# Sheet1.net
KiCad netlist of a schematic drawn in Altium Designer
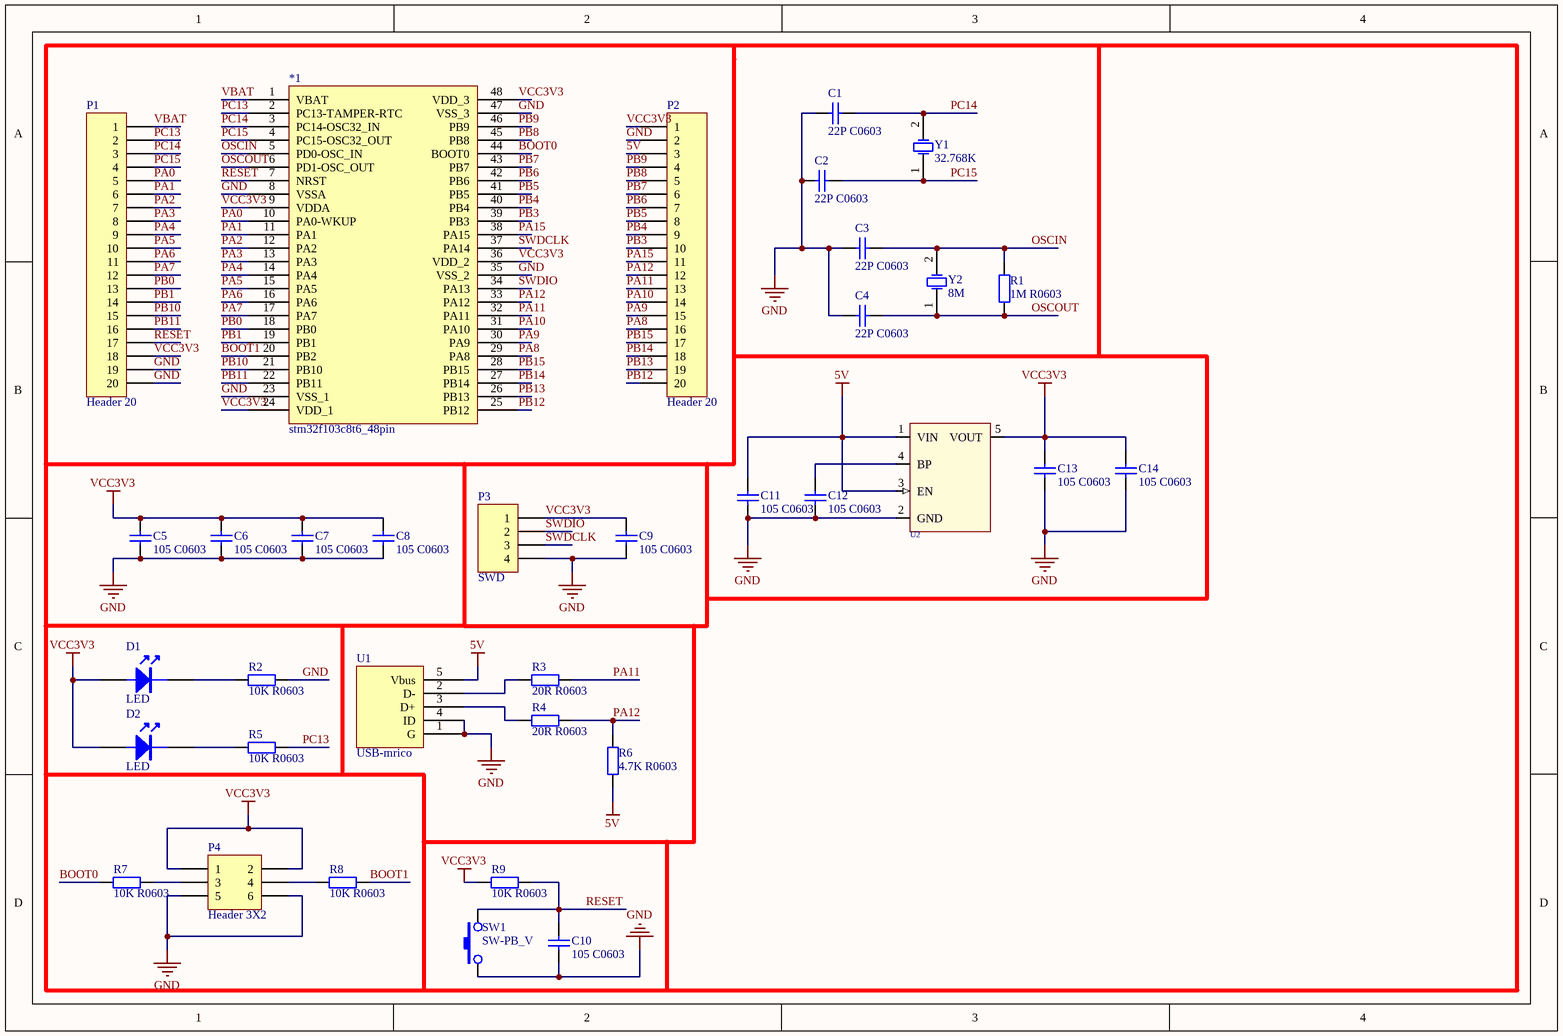
[diagram p0: Sheet1.SchDoc]

(export (version "E")
  (design (tool "Eeschema 10.0.6"))
  (components
    (comp (ref "*1")
      (value "stm32f103c8t6_48pin")
      (footprint "TQFP48 7x7_L")
      (libsource (lib "stm32原理图库") (part "stm32f103c8t6_48pin"))
    )
    (comp (ref "C1")
      (value "22P C0603")
      (footprint "C 0603")
      (fields (field (name "PUBLISHER") "Altium Limited"))
      (libsource (lib "stm32原理图库") (part "Cap"))
    )
    (comp (ref "C2")
      (value "22P C0603")
      (footprint "C 0603")
      (fields (field (name "PUBLISHER") "Altium Limited"))
      (libsource (lib "stm32原理图库") (part "Cap"))
    )
    (comp (ref "C3")
      (value "22P C0603")
      (footprint "C 0603")
      (fields (field (name "PUBLISHER") "Altium Limited"))
      (libsource (lib "stm32原理图库") (part "Cap"))
    )
    (comp (ref "C4")
      (value "22P C0603")
      (footprint "C 0603")
      (fields (field (name "PUBLISHER") "Altium Limited"))
      (libsource (lib "stm32原理图库") (part "Cap"))
    )
    (comp (ref "C5")
      (value "105 C0603")
      (footprint "C 0603")
      (fields (field (name "PUBLISHER") "Altium Limited"))
      (libsource (lib "stm32原理图库") (part "Cap"))
    )
    (comp (ref "C6")
      (value "105 C0603")
      (footprint "C 0603")
      (fields (field (name "PUBLISHER") "Altium Limited"))
      (libsource (lib "stm32原理图库") (part "Cap"))
    )
    (comp (ref "C7")
      (value "105 C0603")
      (footprint "C 0603")
      (fields (field (name "PUBLISHER") "Altium Limited"))
      (libsource (lib "stm32原理图库") (part "Cap"))
    )
    (comp (ref "C8")
      (value "105 C0603")
      (footprint "C 0603")
      (fields (field (name "PUBLISHER") "Altium Limited"))
      (libsource (lib "stm32原理图库") (part "Cap"))
    )
    (comp (ref "C9")
      (value "105 C0603")
      (footprint "C 0603")
      (fields (field (name "PUBLISHER") "Altium Limited"))
      (libsource (lib "stm32原理图库") (part "Cap"))
    )
    (comp (ref "C10")
      (value "105 C0603")
      (footprint "C 0603")
      (fields (field (name "PUBLISHER") "Altium Limited"))
      (libsource (lib "stm32原理图库") (part "Cap"))
    )
    (comp (ref "C11")
      (value "105 C0603")
      (footprint "C 0603")
      (fields (field (name "PUBLISHER") "Altium Limited"))
      (libsource (lib "stm32原理图库") (part "Cap"))
    )
    (comp (ref "C12")
      (value "105 C0603")
      (footprint "C 0603")
      (fields (field (name "PUBLISHER") "Altium Limited"))
      (libsource (lib "stm32原理图库") (part "Cap"))
    )
    (comp (ref "C13")
      (value "105 C0603")
      (footprint "C 0603")
      (fields (field (name "PUBLISHER") "Altium Limited"))
      (libsource (lib "stm32原理图库") (part "Cap"))
    )
    (comp (ref "C14")
      (value "105 C0603")
      (footprint "C 0603")
      (fields (field (name "PUBLISHER") "Altium Limited"))
      (libsource (lib "stm32原理图库") (part "Cap"))
    )
    (comp (ref "D1") (value "LED") (footprint "LED 0805G") (libsource (lib "stm32原理图库") (part "LED")))
    (comp (ref "D2") (value "LED") (footprint "LED 0805G") (libsource (lib "stm32原理图库") (part "LED")))
    (comp (ref "P1")
      (value "Header 20")
      (footprint "HDR1X20")
      (fields (field (name "PUBLISHER") "Altium Limited"))
      (libsource (lib "stm32原理图库") (part "Header1* 20"))
    )
    (comp (ref "P2")
      (value "Header 20")
      (footprint "HDR1X20")
      (fields (field (name "PUBLISHER") "Altium Limited"))
      (libsource (lib "") (part "Header1* 20_1"))
    )
    (comp (ref "P3")
      (value "SWD")
      (footprint "HDR-1X4_H")
      (fields (field (name "PUBLISHER") "Altium Limited"))
      (libsource (lib "stm32原理图库") (part "Header 1*4"))
    )
    (comp (ref "P4")
      (value "Header 3X2")
      (footprint "HDR-3X2")
      (fields (field (name "PUBLISHER") "Altium Limited"))
      (libsource (lib "stm32原理图库") (part "Header 2*3"))
    )
    (comp (ref "R1")
      (value "1M R0603")
      (footprint "R 0603")
      (fields (field (name "PUBLISHER") "Altium Limited"))
      (libsource (lib "") (part "Res2_1"))
    )
    (comp (ref "R2")
      (value "10K R0603")
      (footprint "R 0603")
      (fields (field (name "PUBLISHER") "Altium Limited"))
      (libsource (lib "stm32原理图库") (part "Res2"))
    )
    (comp (ref "R3")
      (value "20R R0603")
      (footprint "R 0603")
      (fields (field (name "PUBLISHER") "Altium Limited"))
      (libsource (lib "stm32原理图库") (part "Res2"))
    )
    (comp (ref "R4")
      (value "20R R0603")
      (footprint "R 0603")
      (fields (field (name "PUBLISHER") "Altium Limited"))
      (libsource (lib "stm32原理图库") (part "Res2"))
    )
    (comp (ref "R5")
      (value "10K R0603")
      (footprint "R 0603")
      (fields (field (name "PUBLISHER") "Altium Limited"))
      (libsource (lib "stm32原理图库") (part "Res2"))
    )
    (comp (ref "R6")
      (value "4.7K R0603")
      (footprint "R 0603")
      (fields (field (name "PUBLISHER") "Altium Limited"))
      (libsource (lib "") (part "Res2_1"))
    )
    (comp (ref "R7")
      (value "10K R0603")
      (footprint "R 0603")
      (fields (field (name "PUBLISHER") "Altium Limited"))
      (libsource (lib "stm32原理图库") (part "Res2"))
    )
    (comp (ref "R8")
      (value "10K R0603")
      (footprint "R 0603")
      (fields (field (name "PUBLISHER") "Altium Limited"))
      (libsource (lib "stm32原理图库") (part "Res2"))
    )
    (comp (ref "R9")
      (value "10K R0603")
      (footprint "R 0603")
      (fields (field (name "PUBLISHER") "Altium Limited"))
      (libsource (lib "stm32原理图库") (part "Res2"))
    )
    (comp (ref "SW1")
      (value "SW-PB_V")
      (footprint "TSW SMD-3*6*2.5")
      (libsource (lib "stm32原理图库") (part "SW-PB_V"))
    )
    (comp (ref "U1")
      (value "USB-mrico")
      (footprint "USB-micro_B")
      (libsource (lib "stm32原理图库") (part "usb-STM"))
    )
    (comp (ref "U2")
      (value "RT9193")
      (footprint "SOT23-5L")
      (fields (field (name "ICA_PARTNUM") "$$2191094$$RT9193-15CU5") (field (name "PART NUMBER") "TMP-13"))
      (libsource (lib "stm32原理图库") (part "RT9193X_5P"))
    )
    (comp (ref "Y1")
      (value "32.768K")
      (footprint "XTAL-49S DIP")
      (fields (field (name "PUBLISHER") "Altium Limited"))
      (libsource (lib "stm32原理图库") (part "XTAL"))
    )
    (comp (ref "Y2")
      (value "8M")
      (footprint "XTAL-49S DIP")
      (fields (field (name "PUBLISHER") "Altium Limited"))
      (libsource (lib "stm32原理图库") (part "XTAL"))
    )
  )
  (nets
    (net (code "1") (name "/BOOT0") (class "Default")
      (node (ref "*1") (pin "44") (pinfunction "BOOT0_44") (pintype "passive"))
      (node (ref "R7") (pin "1") (pinfunction "1_1") (pintype "passive"))
    )
    (net (code "2") (name "/BOOT1") (class "Default")
      (node (ref "*1") (pin "20") (pinfunction "PB2_20") (pintype "passive"))
      (node (ref "R8") (pin "2") (pinfunction "2_2") (pintype "passive"))
    )
    (net (code "3") (name "/OSCIN") (class "Default")
      (node (ref "*1") (pin "5") (pinfunction "PD0-OSC_IN_5") (pintype "passive"))
      (node (ref "C3") (pin "2") (pinfunction "2_2") (pintype "passive"))
      (node (ref "R1") (pin "2") (pinfunction "2_2") (pintype "passive"))
      (node (ref "Y2") (pin "2") (pinfunction "OSC2_2") (pintype "passive"))
    )
    (net (code "4") (name "/OSCOUT") (class "Default")
      (node (ref "*1") (pin "6") (pinfunction "PD1-OSC_OUT_6") (pintype "passive"))
      (node (ref "C4") (pin "2") (pinfunction "2_2") (pintype "passive"))
      (node (ref "R1") (pin "1") (pinfunction "1_1") (pintype "passive"))
      (node (ref "Y2") (pin "1") (pinfunction "OSC1_1") (pintype "passive"))
    )
    (net (code "5") (name "/PA0") (class "Default")
      (node (ref "*1") (pin "10") (pinfunction "PA0-WKUP_10") (pintype "passive"))
      (node (ref "P1") (pin "5") (pinfunction "5_5") (pintype "passive"))
    )
    (net (code "6") (name "/PA1") (class "Default")
      (node (ref "*1") (pin "11") (pinfunction "PA1_11") (pintype "passive"))
      (node (ref "P1") (pin "6") (pinfunction "6_6") (pintype "passive"))
    )
    (net (code "7") (name "/PA2") (class "Default")
      (node (ref "*1") (pin "12") (pinfunction "PA2_12") (pintype "passive"))
      (node (ref "P1") (pin "7") (pinfunction "7_7") (pintype "passive"))
    )
    (net (code "8") (name "/PA3") (class "Default")
      (node (ref "*1") (pin "13") (pinfunction "PA3_13") (pintype "passive"))
      (node (ref "P1") (pin "8") (pinfunction "8_8") (pintype "passive"))
    )
    (net (code "9") (name "/PA4") (class "Default")
      (node (ref "*1") (pin "14") (pinfunction "PA4_14") (pintype "passive"))
      (node (ref "P1") (pin "9") (pinfunction "9_9") (pintype "passive"))
    )
    (net (code "10") (name "/PA5") (class "Default")
      (node (ref "*1") (pin "15") (pinfunction "PA5_15") (pintype "passive"))
      (node (ref "P1") (pin "10") (pinfunction "10_10") (pintype "passive"))
    )
    (net (code "11") (name "/PA6") (class "Default")
      (node (ref "*1") (pin "16") (pinfunction "PA6_16") (pintype "passive"))
      (node (ref "P1") (pin "11") (pinfunction "11_11") (pintype "passive"))
    )
    (net (code "12") (name "/PA7") (class "Default")
      (node (ref "*1") (pin "17") (pinfunction "PA7_17") (pintype "passive"))
      (node (ref "P1") (pin "12") (pinfunction "12_12") (pintype "passive"))
    )
    (net (code "13") (name "/PA8") (class "Default")
      (node (ref "*1") (pin "29") (pinfunction "PA8_29") (pintype "passive"))
      (node (ref "P2") (pin "16") (pinfunction "16_16") (pintype "passive"))
    )
    (net (code "14") (name "/PA9") (class "Default")
      (node (ref "*1") (pin "30") (pinfunction "PA9_30") (pintype "passive"))
      (node (ref "P2") (pin "15") (pinfunction "15_15") (pintype "passive"))
    )
    (net (code "15") (name "/PA10") (class "Default")
      (node (ref "*1") (pin "31") (pinfunction "PA10_31") (pintype "passive"))
      (node (ref "P2") (pin "14") (pinfunction "14_14") (pintype "passive"))
    )
    (net (code "16") (name "/PA11") (class "Default")
      (node (ref "*1") (pin "32") (pinfunction "PA11_32") (pintype "passive"))
      (node (ref "P2") (pin "13") (pinfunction "13_13") (pintype "passive"))
      (node (ref "R3") (pin "2") (pinfunction "2_2") (pintype "passive"))
    )
    (net (code "17") (name "/PA12") (class "Default")
      (node (ref "*1") (pin "33") (pinfunction "PA12_33") (pintype "passive"))
      (node (ref "P2") (pin "12") (pinfunction "12_12") (pintype "passive"))
      (node (ref "R4") (pin "2") (pinfunction "2_2") (pintype "passive"))
      (node (ref "R6") (pin "2") (pinfunction "2_2") (pintype "passive"))
    )
    (net (code "18") (name "/PA15") (class "Default")
      (node (ref "*1") (pin "38") (pinfunction "PA15_38") (pintype "passive"))
      (node (ref "P2") (pin "11") (pinfunction "11_11") (pintype "passive"))
    )
    (net (code "19") (name "/PB0") (class "Default")
      (node (ref "*1") (pin "18") (pinfunction "PB0_18") (pintype "passive"))
      (node (ref "P1") (pin "13") (pinfunction "13_13") (pintype "passive"))
    )
    (net (code "20") (name "/PB1") (class "Default")
      (node (ref "*1") (pin "19") (pinfunction "PB1_19") (pintype "passive"))
      (node (ref "P1") (pin "14") (pinfunction "14_14") (pintype "passive"))
    )
    (net (code "21") (name "/PB3") (class "Default")
      (node (ref "*1") (pin "39") (pinfunction "PB3_39") (pintype "passive"))
      (node (ref "P2") (pin "10") (pinfunction "10_10") (pintype "passive"))
    )
    (net (code "22") (name "/PB4") (class "Default")
      (node (ref "*1") (pin "40") (pinfunction "PB4_40") (pintype "passive"))
      (node (ref "P2") (pin "9") (pinfunction "9_9") (pintype "passive"))
    )
    (net (code "23") (name "/PB5") (class "Default")
      (node (ref "*1") (pin "41") (pinfunction "PB5_41") (pintype "passive"))
      (node (ref "P2") (pin "8") (pinfunction "8_8") (pintype "passive"))
    )
    (net (code "24") (name "/PB6") (class "Default")
      (node (ref "*1") (pin "42") (pinfunction "PB6_42") (pintype "passive"))
      (node (ref "P2") (pin "7") (pinfunction "7_7") (pintype "passive"))
    )
    (net (code "25") (name "/PB7") (class "Default")
      (node (ref "*1") (pin "43") (pinfunction "PB7_43") (pintype "passive"))
      (node (ref "P2") (pin "6") (pinfunction "6_6") (pintype "passive"))
    )
    (net (code "26") (name "/PB8") (class "Default")
      (node (ref "*1") (pin "45") (pinfunction "PB8_45") (pintype "passive"))
      (node (ref "P2") (pin "5") (pinfunction "5_5") (pintype "passive"))
    )
    (net (code "27") (name "/PB9") (class "Default")
      (node (ref "*1") (pin "46") (pinfunction "PB9_46") (pintype "passive"))
      (node (ref "P2") (pin "4") (pinfunction "4_4") (pintype "passive"))
    )
    (net (code "28") (name "/PB10") (class "Default")
      (node (ref "*1") (pin "21") (pinfunction "PB10_21") (pintype "passive"))
      (node (ref "P1") (pin "15") (pinfunction "15_15") (pintype "passive"))
    )
    (net (code "29") (name "/PB11") (class "Default")
      (node (ref "*1") (pin "22") (pinfunction "PB11_22") (pintype "passive"))
      (node (ref "P1") (pin "16") (pinfunction "16_16") (pintype "passive"))
    )
    (net (code "30") (name "/PB12") (class "Default")
      (node (ref "*1") (pin "25") (pinfunction "PB12_25") (pintype "passive"))
      (node (ref "P2") (pin "20") (pinfunction "20_20") (pintype "passive"))
    )
    (net (code "31") (name "/PB13") (class "Default")
      (node (ref "*1") (pin "26") (pinfunction "PB13_26") (pintype "passive"))
      (node (ref "P2") (pin "19") (pinfunction "19_19") (pintype "passive"))
    )
    (net (code "32") (name "/PB14") (class "Default")
      (node (ref "*1") (pin "27") (pinfunction "PB14_27") (pintype "passive"))
      (node (ref "P2") (pin "18") (pinfunction "18_18") (pintype "passive"))
    )
    (net (code "33") (name "/PB15") (class "Default")
      (node (ref "*1") (pin "28") (pinfunction "PB15_28") (pintype "passive"))
      (node (ref "P2") (pin "17") (pinfunction "17_17") (pintype "passive"))
    )
    (net (code "34") (name "/PC13") (class "Default")
      (node (ref "*1") (pin "2") (pinfunction "PC13-TAMPER-RTC_2") (pintype "passive"))
      (node (ref "P1") (pin "2") (pinfunction "2_2") (pintype "passive"))
      (node (ref "R5") (pin "2") (pinfunction "2_2") (pintype "passive"))
    )
    (net (code "35") (name "/PC14") (class "Default")
      (node (ref "*1") (pin "3") (pinfunction "PC14-OSC32_IN_3") (pintype "passive"))
      (node (ref "C1") (pin "2") (pinfunction "2_2") (pintype "passive"))
      (node (ref "P1") (pin "3") (pinfunction "3_3") (pintype "passive"))
      (node (ref "Y1") (pin "2") (pinfunction "OSC2_2") (pintype "passive"))
    )
    (net (code "36") (name "/PC15") (class "Default")
      (node (ref "*1") (pin "4") (pinfunction "PC15-OSC32_OUT_4") (pintype "passive"))
      (node (ref "C2") (pin "2") (pinfunction "2_2") (pintype "passive"))
      (node (ref "P1") (pin "4") (pinfunction "4_4") (pintype "passive"))
      (node (ref "Y1") (pin "1") (pinfunction "OSC1_1") (pintype "passive"))
    )
    (net (code "37") (name "/RESET") (class "Default")
      (node (ref "*1") (pin "7") (pinfunction "NRST_7") (pintype "passive"))
      (node (ref "C10") (pin "2") (pinfunction "2_2") (pintype "passive"))
      (node (ref "P1") (pin "17") (pinfunction "17_17") (pintype "passive"))
      (node (ref "R9") (pin "2") (pinfunction "2_2") (pintype "passive"))
      (node (ref "SW1") (pin "1") (pinfunction "1_1") (pintype "passive"))
    )
    (net (code "38") (name "/SWDCLK") (class "Default")
      (node (ref "*1") (pin "37") (pinfunction "PA14_37") (pintype "passive"))
      (node (ref "P3") (pin "3") (pinfunction "3_3") (pintype "passive"))
    )
    (net (code "39") (name "/SWDIO") (class "Default")
      (node (ref "*1") (pin "34") (pinfunction "PA13_34") (pintype "passive"))
      (node (ref "P3") (pin "2") (pinfunction "2_2") (pintype "passive"))
    )
    (net (code "40") (name "/VBAT") (class "Default")
      (node (ref "*1") (pin "1") (pinfunction "VBAT_1") (pintype "passive"))
      (node (ref "P1") (pin "1") (pinfunction "1_1") (pintype "passive"))
    )
    (net (code "41") (name "5V") (class "Default")
      (node (ref "C11") (pin "2") (pinfunction "2_2") (pintype "passive"))
      (node (ref "P2") (pin "3") (pinfunction "3_3") (pintype "passive"))
      (node (ref "R6") (pin "1") (pinfunction "1_1") (pintype "passive"))
      (node (ref "U1") (pin "5") (pinfunction "Vbus_5") (pintype "passive"))
      (node (ref "U2") (pin "1") (pinfunction "VIN_1") (pintype "power_in"))
      (node (ref "U2") (pin "3") (pinfunction "EN_3") (pintype "input"))
    )
    (net (code "42") (name "GND") (class "Default")
      (node (ref "*1") (pin "23") (pinfunction "VSS_1_23") (pintype "passive"))
      (node (ref "*1") (pin "35") (pinfunction "VSS_2_35") (pintype "passive"))
      (node (ref "*1") (pin "47") (pinfunction "VSS_3_47") (pintype "passive"))
      (node (ref "*1") (pin "8") (pinfunction "VSSA_8") (pintype "passive"))
      (node (ref "C1") (pin "1") (pinfunction "1_1") (pintype "passive"))
      (node (ref "C10") (pin "1") (pinfunction "1_1") (pintype "passive"))
      (node (ref "C11") (pin "1") (pinfunction "1_1") (pintype "passive"))
      (node (ref "C12") (pin "1") (pinfunction "1_1") (pintype "passive"))
      (node (ref "C13") (pin "1") (pinfunction "1_1") (pintype "passive"))
      (node (ref "C14") (pin "1") (pinfunction "1_1") (pintype "passive"))
      (node (ref "C2") (pin "1") (pinfunction "1_1") (pintype "passive"))
      (node (ref "C3") (pin "1") (pinfunction "1_1") (pintype "passive"))
      (node (ref "C4") (pin "1") (pinfunction "1_1") (pintype "passive"))
      (node (ref "C5") (pin "1") (pinfunction "1_1") (pintype "passive"))
      (node (ref "C6") (pin "1") (pinfunction "1_1") (pintype "passive"))
      (node (ref "C7") (pin "1") (pinfunction "1_1") (pintype "passive"))
      (node (ref "C8") (pin "1") (pinfunction "1_1") (pintype "passive"))
      (node (ref "C9") (pin "1") (pinfunction "1_1") (pintype "passive"))
      (node (ref "P1") (pin "19") (pinfunction "19_19") (pintype "passive"))
      (node (ref "P1") (pin "20") (pinfunction "20_20") (pintype "passive"))
      (node (ref "P2") (pin "2") (pinfunction "2_2") (pintype "passive"))
      (node (ref "P3") (pin "4") (pinfunction "4_4") (pintype "passive"))
      (node (ref "P4") (pin "5") (pinfunction "5_5") (pintype "passive"))
      (node (ref "P4") (pin "6") (pinfunction "6_6") (pintype "passive"))
      (node (ref "R2") (pin "2") (pinfunction "2_2") (pintype "passive"))
      (node (ref "SW1") (pin "2") (pinfunction "2_2") (pintype "passive"))
      (node (ref "U1") (pin "1") (pinfunction "G_1") (pintype "passive"))
      (node (ref "U1") (pin "4") (pinfunction "ID_4") (pintype "passive"))
      (node (ref "U2") (pin "2") (pinfunction "GND_2") (pintype "power_in"))
    )
    (net (code "43") (name "Net-(D1-Pad2)") (class "Default")
      (node (ref "D1") (pin "2") (pinfunction "2_2") (pintype "passive"))
      (node (ref "R2") (pin "1") (pinfunction "1_1") (pintype "passive"))
    )
    (net (code "44") (name "Net-(D2-Pad2)") (class "Default")
      (node (ref "D2") (pin "2") (pinfunction "2_2") (pintype "passive"))
      (node (ref "R5") (pin "1") (pinfunction "1_1") (pintype "passive"))
    )
    (net (code "45") (name "Net-(P4-Pad3)") (class "Default")
      (node (ref "P4") (pin "3") (pinfunction "3_3") (pintype "passive"))
      (node (ref "R7") (pin "2") (pinfunction "2_2") (pintype "passive"))
    )
    (net (code "46") (name "Net-(P4-Pad4)") (class "Default")
      (node (ref "P4") (pin "4") (pinfunction "4_4") (pintype "passive"))
      (node (ref "R8") (pin "1") (pinfunction "1_1") (pintype "passive"))
    )
    (net (code "47") (name "Net-(U1-D+)") (class "Default")
      (node (ref "R4") (pin "1") (pinfunction "1_1") (pintype "passive"))
      (node (ref "U1") (pin "3") (pinfunction "D+_3") (pintype "passive"))
    )
    (net (code "48") (name "Net-(U1-D-)") (class "Default")
      (node (ref "R3") (pin "1") (pinfunction "1_1") (pintype "passive"))
      (node (ref "U1") (pin "2") (pinfunction "D-_2") (pintype "passive"))
    )
    (net (code "49") (name "Net-(U2-BP)") (class "Default")
      (node (ref "C12") (pin "2") (pinfunction "2_2") (pintype "passive"))
      (node (ref "U2") (pin "4") (pinfunction "BP_4") (pintype "passive"))
    )
    (net (code "50") (name "VCC3V3") (class "Default")
      (node (ref "*1") (pin "24") (pinfunction "VDD_1_24") (pintype "passive"))
      (node (ref "*1") (pin "36") (pinfunction "VDD_2_36") (pintype "passive"))
      (node (ref "*1") (pin "48") (pinfunction "VDD_3_48") (pintype "passive"))
      (node (ref "*1") (pin "9") (pinfunction "VDDA_9") (pintype "passive"))
      (node (ref "C13") (pin "2") (pinfunction "2_2") (pintype "passive"))
      (node (ref "C14") (pin "2") (pinfunction "2_2") (pintype "passive"))
      (node (ref "C5") (pin "2") (pinfunction "2_2") (pintype "passive"))
      (node (ref "C6") (pin "2") (pinfunction "2_2") (pintype "passive"))
      (node (ref "C7") (pin "2") (pinfunction "2_2") (pintype "passive"))
      (node (ref "C8") (pin "2") (pinfunction "2_2") (pintype "passive"))
      (node (ref "C9") (pin "2") (pinfunction "2_2") (pintype "passive"))
      (node (ref "D1") (pin "1") (pinfunction "1_1") (pintype "passive"))
      (node (ref "D2") (pin "1") (pinfunction "1_1") (pintype "passive"))
      (node (ref "P1") (pin "18") (pinfunction "18_18") (pintype "passive"))
      (node (ref "P2") (pin "1") (pinfunction "1_1") (pintype "passive"))
      (node (ref "P3") (pin "1") (pinfunction "1_1") (pintype "passive"))
      (node (ref "P4") (pin "1") (pinfunction "1_1") (pintype "passive"))
      (node (ref "P4") (pin "2") (pinfunction "2_2") (pintype "passive"))
      (node (ref "R9") (pin "1") (pinfunction "1_1") (pintype "passive"))
      (node (ref "U2") (pin "5") (pinfunction "VOUT_5") (pintype "power_in"))
    )
  )
)
